# Chip_v1_unevenFootprint.net
KiCad netlist of a schematic drawn in Altium Designer
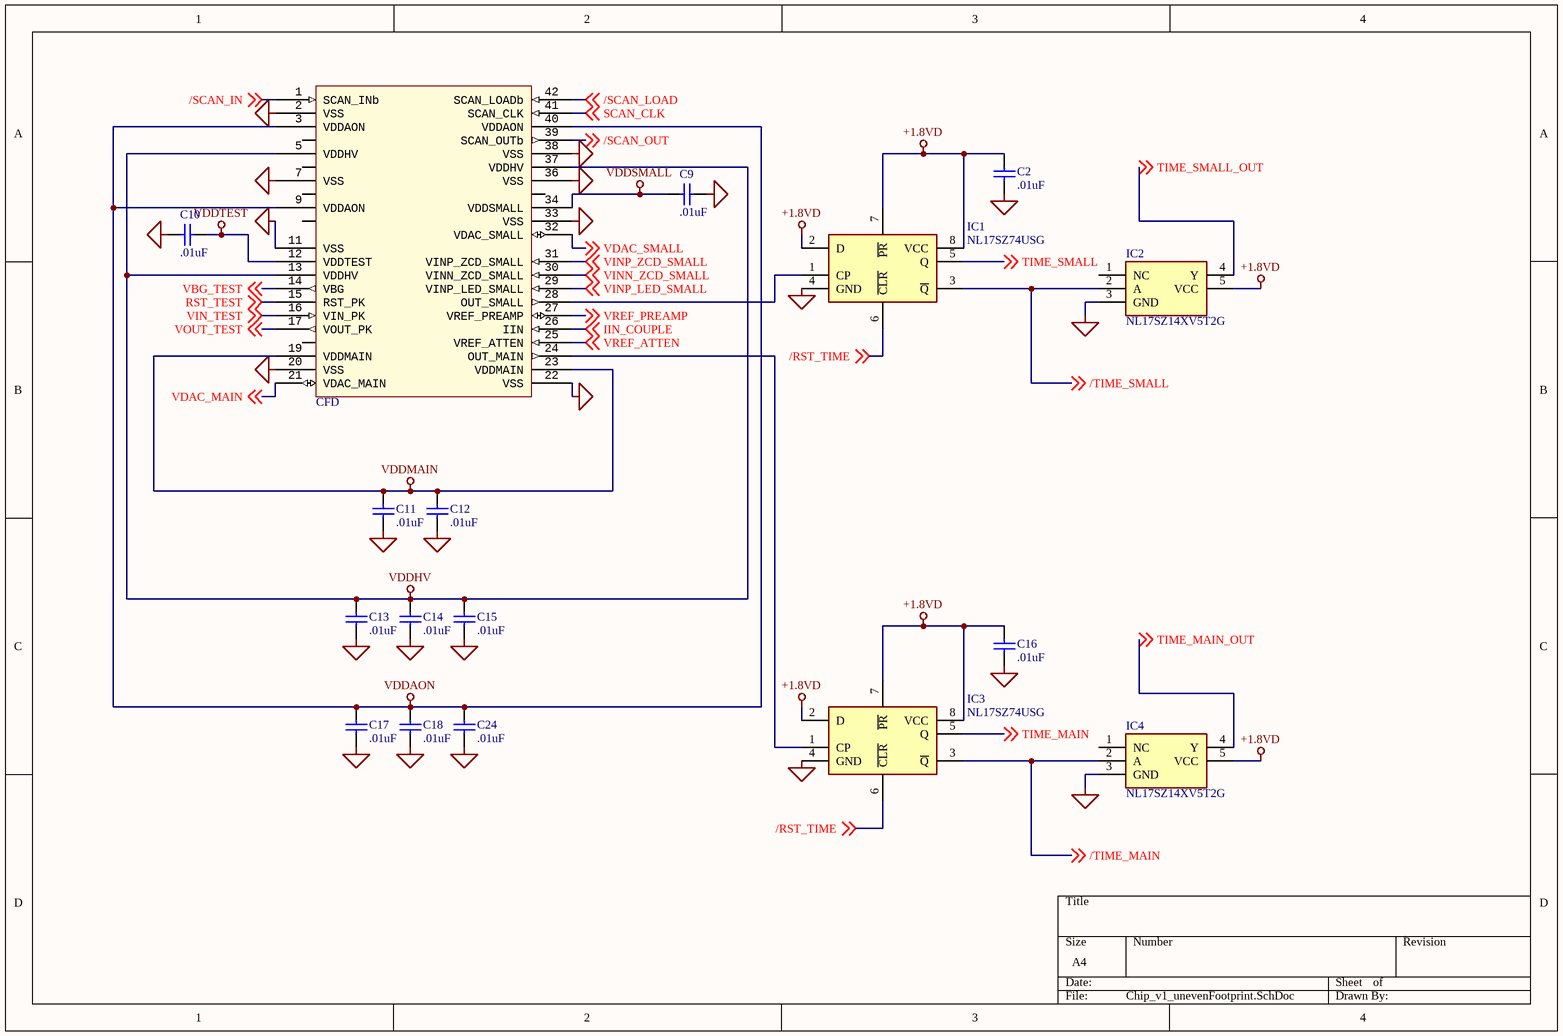
[diagram p0: Chip_v1_unevenFootprint.SchDoc]

(export (version "E")
  (design (tool "Eeschema 10.0.6"))
  (components
    (comp (ref "C2")
      (value ".01uF")
      (footprint "CAPC2013X140X45NL15T25")
      (description "0402")
      (fields (field (name "PART NUMBER") "GRM21BR71A106KE51L") (field (name "MANUFACTURER") "Murata"))
      (libsource (lib "Altium Content Vault") (part "CAP"))
    )
    (comp (ref "C9")
      (value ".01uF")
      (footprint "CAPC2013X140X45NL15T25")
      (description "0402")
      (fields (field (name "PART NUMBER") "GRM21BR71A106KE51L") (field (name "MANUFACTURER") "Murata"))
      (libsource (lib "Altium Content Vault") (part "CAP"))
    )
    (comp (ref "C10")
      (value ".01uF")
      (footprint "CAPC2013X140X45NL15T25")
      (description "0402")
      (fields (field (name "PART NUMBER") "GRM21BR71A106KE51L") (field (name "MANUFACTURER") "Murata"))
      (libsource (lib "Altium Content Vault") (part "CAP"))
    )
    (comp (ref "C11")
      (value ".01uF")
      (footprint "CAPC2013X140X45NL15T25")
      (description "0402")
      (fields (field (name "PART NUMBER") "GRM21BR71A106KE51L") (field (name "MANUFACTURER") "Murata"))
      (libsource (lib "Altium Content Vault") (part "CAP"))
    )
    (comp (ref "C12")
      (value ".01uF")
      (footprint "CAPC2013X140X45NL15T25")
      (description "0402")
      (fields (field (name "PART NUMBER") "GRM21BR71A106KE51L") (field (name "MANUFACTURER") "Murata"))
      (libsource (lib "Altium Content Vault") (part "CAP"))
    )
    (comp (ref "C13")
      (value ".01uF")
      (footprint "CAPC2013X140X45NL15T25")
      (description "0402")
      (fields (field (name "PART NUMBER") "GRM21BR71A106KE51L") (field (name "MANUFACTURER") "Murata"))
      (libsource (lib "Altium Content Vault") (part "CAP"))
    )
    (comp (ref "C14")
      (value ".01uF")
      (footprint "CAPC2013X140X45NL15T25")
      (description "0402")
      (fields (field (name "PART NUMBER") "GRM21BR71A106KE51L") (field (name "MANUFACTURER") "Murata"))
      (libsource (lib "Altium Content Vault") (part "CAP"))
    )
    (comp (ref "C15")
      (value ".01uF")
      (footprint "CAPC2013X140X45NL15T25")
      (description "0402")
      (fields (field (name "PART NUMBER") "GRM21BR71A106KE51L") (field (name "MANUFACTURER") "Murata"))
      (libsource (lib "Altium Content Vault") (part "CAP"))
    )
    (comp (ref "C16")
      (value ".01uF")
      (footprint "CAPC2013X140X45NL15T25")
      (description "0402")
      (fields (field (name "PART NUMBER") "GRM21BR71A106KE51L") (field (name "MANUFACTURER") "Murata"))
      (libsource (lib "Altium Content Vault") (part "CAP"))
    )
    (comp (ref "C17")
      (value ".01uF")
      (footprint "CAPC2013X140X45NL15T25")
      (description "0402")
      (fields (field (name "PART NUMBER") "GRM21BR71A106KE51L") (field (name "MANUFACTURER") "Murata"))
      (libsource (lib "Altium Content Vault") (part "CAP"))
    )
    (comp (ref "C18")
      (value ".01uF")
      (footprint "CAPC2013X140X45NL15T25")
      (description "0402")
      (fields (field (name "PART NUMBER") "GRM21BR71A106KE51L") (field (name "MANUFACTURER") "Murata"))
      (libsource (lib "Altium Content Vault") (part "CAP"))
    )
    (comp (ref "C24")
      (value ".01uF")
      (footprint "CAPC2013X140X45NL15T25")
      (description "0402")
      (fields (field (name "PART NUMBER") "GRM21BR71A106KE51L") (field (name "MANUFACTURER") "Murata"))
      (libsource (lib "Altium Content Vault") (part "CAP"))
    )
    (comp (ref "CHIP1")
      (value "CFD")
      (footprint "QFN50P700X700X80_HS-43N")
      (libsource (lib "intlib") (part "CFD"))
    )
    (comp (ref "IC1")
      (value "NL17SZ74USG")
      (footprint "SamacSys:SOP50P310X90-8N")
      (description "Flip Flops 1.65-5.5V CMOS Single D-Type")
      (libsource (lib "SamacSys") (part "NL17SZ74USG"))
    )
    (comp (ref "IC2")
      (value "NL17SZ14XV5T2G")
      (footprint "SamacSys:SOTFL50P160X60-5N")
      (description "Integrated Circuit")
      (fields (field (name "MOUSER2 PART NUMBER") "863-NL17SZ14XV5T2G"))
      (libsource (lib "SamacSys") (part "NL17SZ14XV5T2G"))
    )
    (comp (ref "IC3")
      (value "NL17SZ74USG")
      (footprint "SamacSys:SOP50P310X90-8N")
      (description "Flip Flops 1.65-5.5V CMOS Single D-Type")
      (libsource (lib "SamacSys") (part "NL17SZ74USG"))
    )
    (comp (ref "IC4")
      (value "NL17SZ14XV5T2G")
      (footprint "SamacSys:SOTFL50P160X60-5N")
      (description "Integrated Circuit")
      (fields (field (name "MOUSER2 PART NUMBER") "863-NL17SZ14XV5T2G"))
      (libsource (lib "SamacSys") (part "NL17SZ14XV5T2G"))
    )
  )
  (nets
    (net (code "1") (name "+1.8VD") (class "Default")
      (node (ref "C16") (pin "2") (pinfunction "2_2") (pintype "passive"))
      (node (ref "C2") (pin "2") (pinfunction "2_2") (pintype "passive"))
      (node (ref "IC1") (pin "2") (pinfunction "D_2") (pintype "passive"))
      (node (ref "IC1") (pin "7") (pinfunction "~{PR}_7") (pintype "passive"))
      (node (ref "IC1") (pin "8") (pinfunction "VCC_8") (pintype "passive"))
      (node (ref "IC2") (pin "5") (pinfunction "VCC_5") (pintype "passive"))
      (node (ref "IC3") (pin "2") (pinfunction "D_2") (pintype "passive"))
      (node (ref "IC3") (pin "7") (pinfunction "~{PR}_7") (pintype "passive"))
      (node (ref "IC3") (pin "8") (pinfunction "VCC_8") (pintype "passive"))
      (node (ref "IC4") (pin "5") (pinfunction "VCC_5") (pintype "passive"))
    )
    (net (code "2") (name "GND") (class "Default")
      (node (ref "C10") (pin "1") (pinfunction "1_1") (pintype "passive"))
      (node (ref "C11") (pin "1") (pinfunction "1_1") (pintype "passive"))
      (node (ref "C12") (pin "1") (pinfunction "1_1") (pintype "passive"))
      (node (ref "C13") (pin "1") (pinfunction "1_1") (pintype "passive"))
      (node (ref "C14") (pin "1") (pinfunction "1_1") (pintype "passive"))
      (node (ref "C15") (pin "1") (pinfunction "1_1") (pintype "passive"))
      (node (ref "C16") (pin "1") (pinfunction "1_1") (pintype "passive"))
      (node (ref "C17") (pin "1") (pinfunction "1_1") (pintype "passive"))
      (node (ref "C18") (pin "1") (pinfunction "1_1") (pintype "passive"))
      (node (ref "C2") (pin "1") (pinfunction "1_1") (pintype "passive"))
      (node (ref "C24") (pin "1") (pinfunction "1_1") (pintype "passive"))
      (node (ref "C9") (pin "1") (pinfunction "1_1") (pintype "passive"))
      (node (ref "CHIP1") (pin "11") (pinfunction "VSS_11") (pintype "power_in"))
      (node (ref "CHIP1") (pin "2") (pinfunction "VSS_2") (pintype "power_in"))
      (node (ref "CHIP1") (pin "20") (pinfunction "VSS_20") (pintype "power_in"))
      (node (ref "CHIP1") (pin "22") (pinfunction "VSS_22") (pintype "power_in"))
      (node (ref "CHIP1") (pin "33") (pinfunction "VSS_33") (pintype "power_in"))
      (node (ref "CHIP1") (pin "36") (pinfunction "VSS_36") (pintype "power_in"))
      (node (ref "CHIP1") (pin "38") (pinfunction "VSS_38") (pintype "power_in"))
      (node (ref "CHIP1") (pin "7") (pinfunction "VSS_7") (pintype "power_in"))
      (node (ref "IC1") (pin "4") (pinfunction "GND_4") (pintype "passive"))
      (node (ref "IC2") (pin "3") (pinfunction "GND_3") (pintype "passive"))
      (node (ref "IC3") (pin "4") (pinfunction "GND_4") (pintype "passive"))
      (node (ref "IC4") (pin "3") (pinfunction "GND_3") (pintype "passive"))
    )
    (net (code "3") (name "IIN_COUPLE") (class "Default")
      (node (ref "CHIP1") (pin "26") (pinfunction "IIN_26") (pintype "input"))
    )
    (net (code "4") (name "Net-(CHIP1-OUT_MAIN)") (class "Default")
      (node (ref "CHIP1") (pin "24") (pinfunction "OUT_MAIN_24") (pintype "output"))
      (node (ref "IC3") (pin "1") (pinfunction "CP_1") (pintype "passive"))
    )
    (net (code "5") (name "Net-(CHIP1-OUT_SMALL)") (class "Default")
      (node (ref "CHIP1") (pin "28") (pinfunction "OUT_SMALL_28") (pintype "output"))
      (node (ref "IC1") (pin "1") (pinfunction "CP_1") (pintype "passive"))
    )
    (net (code "6") (name "RST_TEST") (class "Default")
      (node (ref "CHIP1") (pin "15") (pinfunction "RST_PK_15") (pintype "passive"))
    )
    (net (code "7") (name "SCAN_CLK") (class "Default")
      (node (ref "CHIP1") (pin "41") (pinfunction "SCAN_CLK_41") (pintype "input"))
    )
    (net (code "8") (name "TIME_MAIN") (class "Default")
      (node (ref "IC3") (pin "5") (pinfunction "Q_5") (pintype "passive"))
    )
    (net (code "9") (name "TIME_MAIN_OUT") (class "Default")
      (node (ref "IC4") (pin "4") (pinfunction "Y_4") (pintype "passive"))
    )
    (net (code "10") (name "TIME_SMALL") (class "Default")
      (node (ref "IC1") (pin "5") (pinfunction "Q_5") (pintype "passive"))
    )
    (net (code "11") (name "TIME_SMALL_OUT") (class "Default")
      (node (ref "IC2") (pin "4") (pinfunction "Y_4") (pintype "passive"))
    )
    (net (code "12") (name "VBG_TEST") (class "Default")
      (node (ref "CHIP1") (pin "14") (pinfunction "VBG_14") (pintype "output"))
    )
    (net (code "13") (name "VDAC_MAIN") (class "Default")
      (node (ref "CHIP1") (pin "21") (pinfunction "VDAC_MAIN_21") (pintype "bidirectional"))
    )
    (net (code "14") (name "VDAC_SMALL") (class "Default")
      (node (ref "CHIP1") (pin "32") (pinfunction "VDAC_SMALL_32") (pintype "bidirectional"))
    )
    (net (code "15") (name "VDDAON") (class "Default")
      (node (ref "C17") (pin "2") (pinfunction "2_2") (pintype "passive"))
      (node (ref "C18") (pin "2") (pinfunction "2_2") (pintype "passive"))
      (node (ref "C24") (pin "2") (pinfunction "2_2") (pintype "passive"))
      (node (ref "CHIP1") (pin "3") (pinfunction "VDDAON_3") (pintype "power_in"))
      (node (ref "CHIP1") (pin "40") (pinfunction "VDDAON_40") (pintype "power_in"))
      (node (ref "CHIP1") (pin "9") (pinfunction "VDDAON_9") (pintype "power_in"))
    )
    (net (code "16") (name "VDDHV") (class "Default")
      (node (ref "C13") (pin "2") (pinfunction "2_2") (pintype "passive"))
      (node (ref "C14") (pin "2") (pinfunction "2_2") (pintype "passive"))
      (node (ref "C15") (pin "2") (pinfunction "2_2") (pintype "passive"))
      (node (ref "CHIP1") (pin "13") (pinfunction "VDDHV_13") (pintype "power_in"))
      (node (ref "CHIP1") (pin "37") (pinfunction "VDDHV_37") (pintype "power_in"))
      (node (ref "CHIP1") (pin "5") (pinfunction "VDDHV_5") (pintype "power_in"))
    )
    (net (code "17") (name "VDDMAIN") (class "Default")
      (node (ref "C11") (pin "2") (pinfunction "2_2") (pintype "passive"))
      (node (ref "C12") (pin "2") (pinfunction "2_2") (pintype "passive"))
      (node (ref "CHIP1") (pin "19") (pinfunction "VDDMAIN_19") (pintype "power_in"))
      (node (ref "CHIP1") (pin "23") (pinfunction "VDDMAIN_23") (pintype "power_in"))
    )
    (net (code "18") (name "VDDSMALL") (class "Default")
      (node (ref "C9") (pin "2") (pinfunction "2_2") (pintype "passive"))
      (node (ref "CHIP1") (pin "34") (pinfunction "VDDSMALL_34") (pintype "power_in"))
    )
    (net (code "19") (name "VDDTEST") (class "Default")
      (node (ref "C10") (pin "2") (pinfunction "2_2") (pintype "passive"))
      (node (ref "CHIP1") (pin "12") (pinfunction "VDDTEST_12") (pintype "power_in"))
    )
    (net (code "20") (name "VINN_ZCD_SMALL") (class "Default")
      (node (ref "CHIP1") (pin "30") (pinfunction "VINN_ZCD_SMALL_30") (pintype "input"))
    )
    (net (code "21") (name "VINP_LED_SMALL") (class "Default")
      (node (ref "CHIP1") (pin "29") (pinfunction "VINP_LED_SMALL_29") (pintype "input"))
    )
    (net (code "22") (name "VINP_ZCD_SMALL") (class "Default")
      (node (ref "CHIP1") (pin "31") (pinfunction "VINP_ZCD_SMALL_31") (pintype "input"))
    )
    (net (code "23") (name "VIN_TEST") (class "Default")
      (node (ref "CHIP1") (pin "16") (pinfunction "VIN_PK_16") (pintype "input"))
    )
    (net (code "24") (name "VOUT_TEST") (class "Default")
      (node (ref "CHIP1") (pin "17") (pinfunction "VOUT_PK_17") (pintype "output"))
    )
    (net (code "25") (name "VREF_ATTEN") (class "Default")
      (node (ref "CHIP1") (pin "25") (pinfunction "VREF_ATTEN_25") (pintype "input"))
    )
    (net (code "26") (name "VREF_PREAMP") (class "Default")
      (node (ref "CHIP1") (pin "27") (pinfunction "VREF_PREAMP_27") (pintype "bidirectional"))
    )
    (net (code "27") (name "unconnected-(CHIP1-Pad4)") (class "Default")
      (node (ref "CHIP1") (pin "4") (pintype "tri_state"))
    )
    (net (code "28") (name "unconnected-(CHIP1-Pad6)") (class "Default")
      (node (ref "CHIP1") (pin "6") (pintype "tri_state"))
    )
    (net (code "29") (name "unconnected-(CHIP1-Pad8)") (class "Default")
      (node (ref "CHIP1") (pin "8") (pintype "tri_state"))
    )
    (net (code "30") (name "unconnected-(CHIP1-Pad10)") (class "Default")
      (node (ref "CHIP1") (pin "10") (pintype "tri_state"))
    )
    (net (code "31") (name "unconnected-(CHIP1-Pad18)") (class "Default")
      (node (ref "CHIP1") (pin "18") (pintype "tri_state"))
    )
    (net (code "32") (name "unconnected-(CHIP1-Pad35)") (class "Default")
      (node (ref "CHIP1") (pin "35") (pintype "tri_state"))
    )
    (net (code "33") (name "unconnected-(IC2-NC-Pad1)") (class "Default")
      (node (ref "IC2") (pin "1") (pinfunction "NC_1") (pintype "passive"))
    )
    (net (code "34") (name "unconnected-(IC4-NC-Pad1)") (class "Default")
      (node (ref "IC4") (pin "1") (pinfunction "NC_1") (pintype "passive"))
    )
    (net (code "35") (name "{slash}RST_TIME") (class "Default")
      (node (ref "IC1") (pin "6") (pinfunction "~{CLR}_6") (pintype "passive"))
      (node (ref "IC3") (pin "6") (pinfunction "~{CLR}_6") (pintype "passive"))
    )
    (net (code "36") (name "{slash}SCAN_IN") (class "Default")
      (node (ref "CHIP1") (pin "1") (pinfunction "SCAN_INb_1") (pintype "input"))
    )
    (net (code "37") (name "{slash}SCAN_LOAD") (class "Default")
      (node (ref "CHIP1") (pin "42") (pinfunction "SCAN_LOADb_42") (pintype "input"))
    )
    (net (code "38") (name "{slash}SCAN_OUT") (class "Default")
      (node (ref "CHIP1") (pin "39") (pinfunction "SCAN_OUTb_39") (pintype "output"))
    )
    (net (code "39") (name "{slash}TIME_MAIN") (class "Default")
      (node (ref "IC3") (pin "3") (pinfunction "~{Q}_3") (pintype "passive"))
      (node (ref "IC4") (pin "2") (pinfunction "A_2") (pintype "passive"))
    )
    (net (code "40") (name "{slash}TIME_SMALL") (class "Default")
      (node (ref "IC1") (pin "3") (pinfunction "~{Q}_3") (pintype "passive"))
      (node (ref "IC2") (pin "2") (pinfunction "A_2") (pintype "passive"))
    )
  )
)
